# Esquema.net
KiCad netlist of a schematic drawn in EAGLE
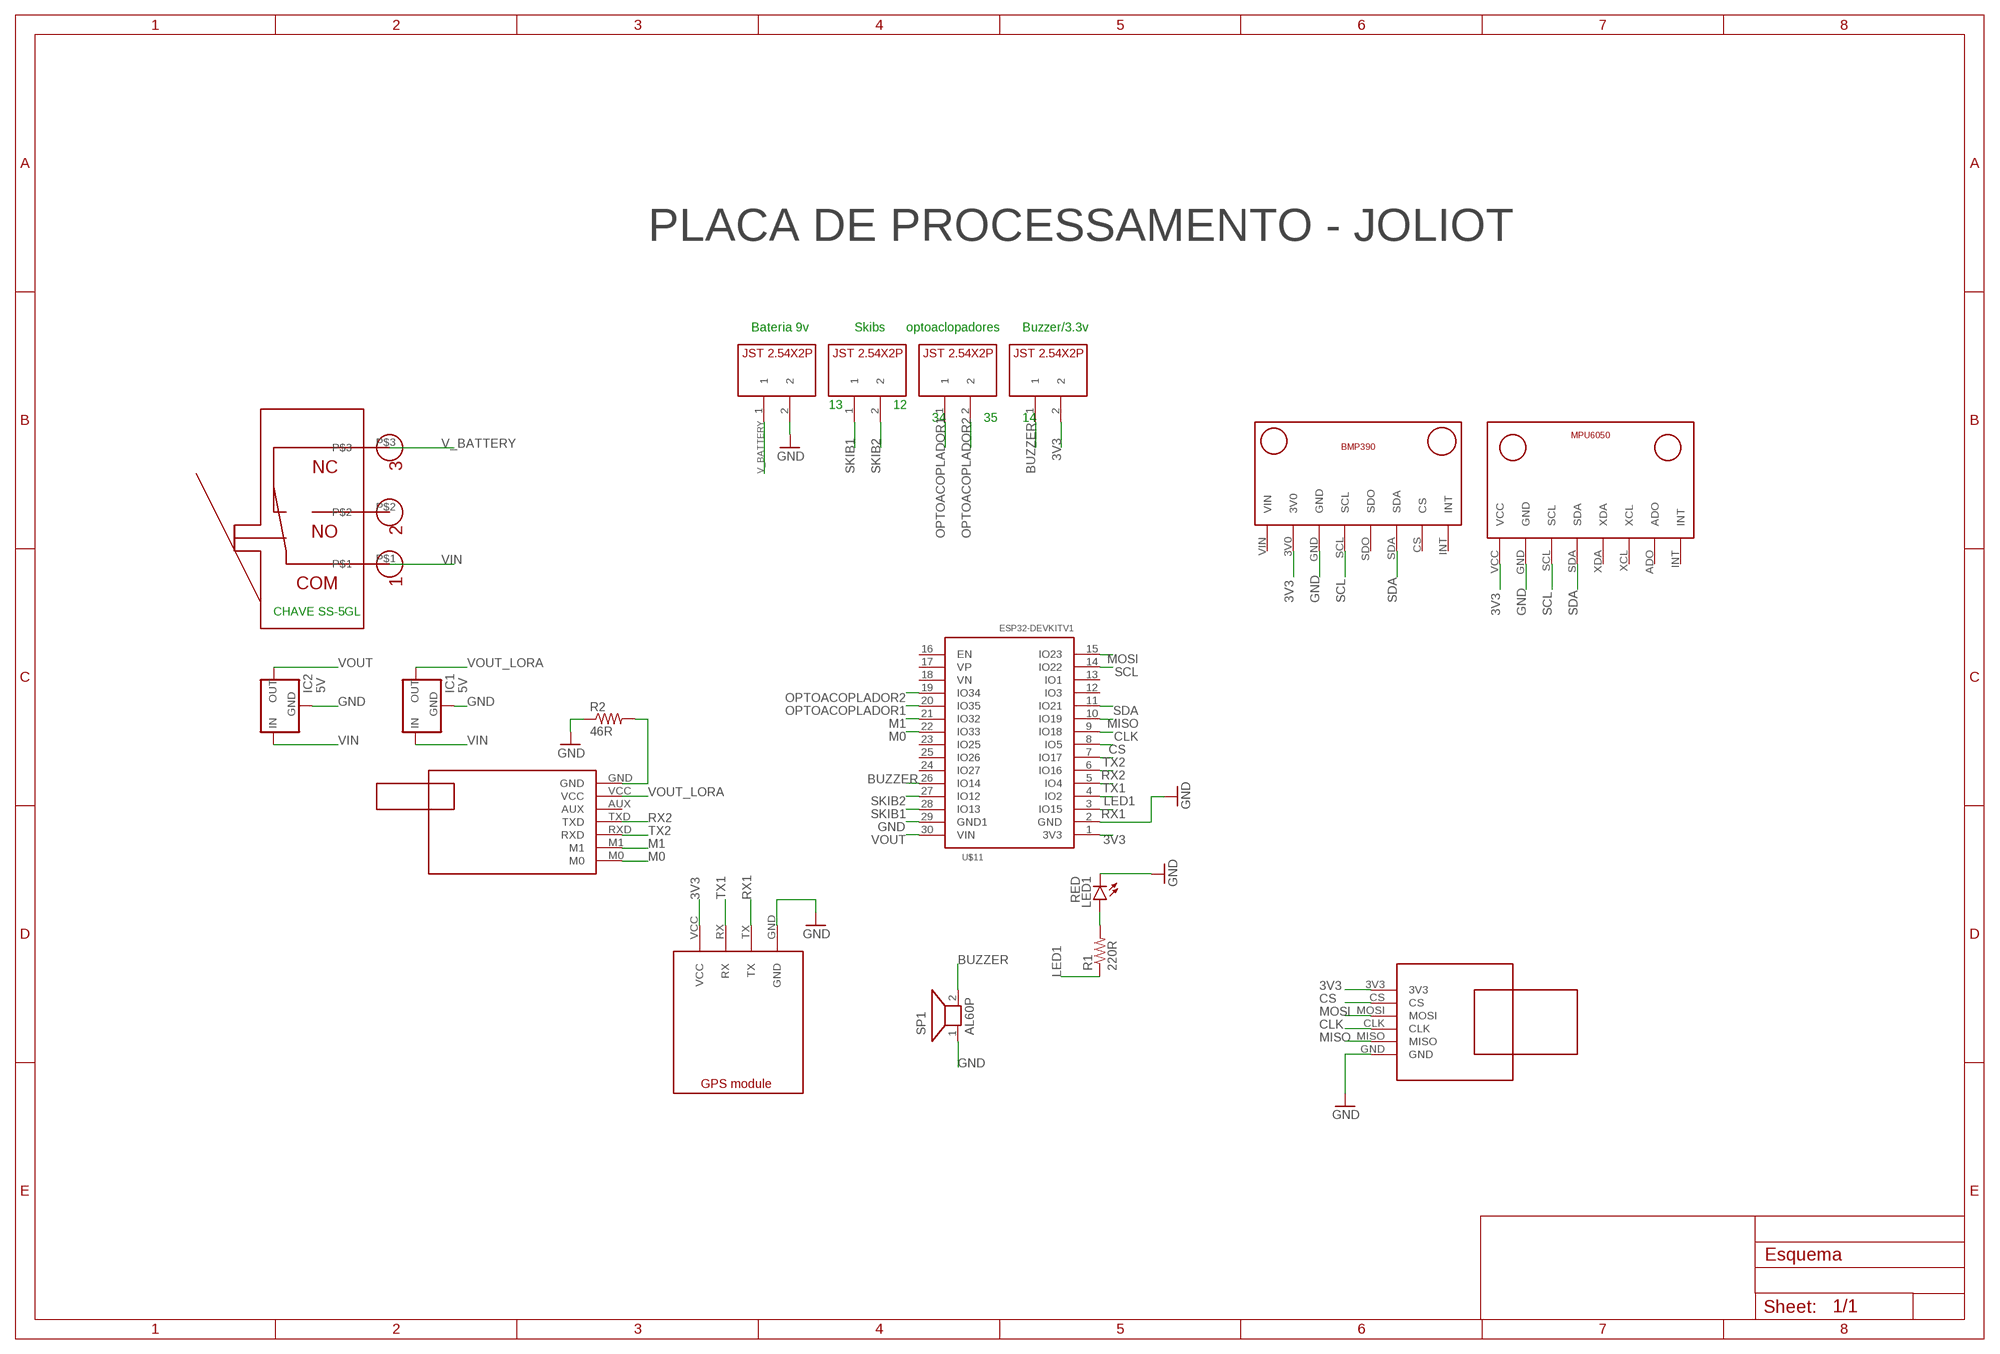
[diagram p0: schematic, sheet 1]

(export (version "E")
  (design (tool "Eeschema 10.0.6"))
  (components
    (comp (ref "IC1")
      (value "5V")
      (footprint "eagle-import:78XXL")
      (libsource (lib "eagle-import") (part "78XXL"))
    )
    (comp (ref "IC2")
      (value "5V")
      (footprint "eagle-import:78XXL")
      (libsource (lib "eagle-import") (part "78XXL"))
    )
    (comp (ref "LED1")
      (value "RED")
      (footprint "eagle-import:LED5MM")
      (libsource (lib "eagle-import") (part "LED5MM"))
    )
    (comp (ref "R1")
      (value "220R")
      (footprint "eagle-import:0309_12")
      (libsource (lib "eagle-import") (part "R-US_0309/12"))
    )
    (comp (ref "R2")
      (value "46R")
      (footprint "eagle-import:0309_12")
      (libsource (lib "eagle-import") (part "R-US_0309/12"))
    )
    (comp (ref "SP1")
      (value "AL60P")
      (footprint "eagle-import:AL60P")
      (libsource (lib "eagle-import") (part "AL60P"))
    )
    (comp (ref "U$1")
      (value "BMP390V1")
      (footprint "eagle-import:BMP390_FOOTPRINT")
      (libsource (lib "eagle-import") (part "BMP390V1"))
    )
    (comp (ref "U$2")
      (value "E22-400T30D")
      (footprint "eagle-import:E22-400T30D_FOOTPRINT")
      (libsource (lib "eagle-import") (part "E22-400T30D"))
    )
    (comp (ref "U$3")
      (value "GPS_MODULE")
      (footprint "eagle-import:GPS_MODULE_FOOTPRINT")
      (libsource (lib "eagle-import") (part "GPS_MODULE"))
    )
    (comp (ref "U$4")
      (value "JST2.54X2P")
      (footprint "eagle-import:JST2.54X2P_FOOTPRINT")
      (libsource (lib "eagle-import") (part "JST2.54X2P"))
    )
    (comp (ref "U$5")
      (value "JST2.54X2P")
      (footprint "eagle-import:JST2.54X2P_FOOTPRINT")
      (libsource (lib "eagle-import") (part "JST2.54X2P"))
    )
    (comp (ref "U$6")
      (value "JST2.54X2P")
      (footprint "eagle-import:JST2.54X2P_FOOTPRINT")
      (libsource (lib "eagle-import") (part "JST2.54X2P"))
    )
    (comp (ref "U$7")
      (value "JST2.54X2P")
      (footprint "eagle-import:JST2.54X2P_FOOTPRINT")
      (libsource (lib "eagle-import") (part "JST2.54X2P"))
    )
    (comp (ref "U$8")
      (value "MICROSD_SMALL_READER")
      (footprint "eagle-import:MICROSD_SMALL_READER_FOOTPRINT")
      (libsource (lib "eagle-import") (part "MICROSD_SMALL_READER"))
    )
    (comp (ref "U$9")
      (value "MPU6050V1")
      (footprint "eagle-import:MPU6050_FOOTPRINT")
      (libsource (lib "eagle-import") (part "MPU6050V1"))
    )
    (comp (ref "U$11")
      (value "ESP32DEVKITV1")
      (footprint "eagle-import:ESP32-DEVKITV1")
      (libsource (lib "eagle-import") (part "ESP32DEVKITV1"))
    )
    (comp (ref "U$12")
      (value "CHAVE_SS-5GL")
      (footprint "eagle-import:CHAVESS-5GL")
      (libsource (lib "eagle-import") (part "CHAVE_SS-5GL"))
    )
  )
  (nets
    (net (code "1") (name "/3V3") (class "Default")
      (node (ref "U$1") (pin "3V0") (pinfunction "3V0_3V0") (pintype "bidirectional"))
      (node (ref "U$11") (pin "1") (pinfunction "3V3_1") (pintype "bidirectional"))
      (node (ref "U$3") (pin "VCC") (pinfunction "VCC_VCC") (pintype "bidirectional"))
      (node (ref "U$4") (pin "2") (pinfunction "2_2") (pintype "bidirectional"))
      (node (ref "U$8") (pin "3V3") (pinfunction "3V3_3V3") (pintype "bidirectional"))
      (node (ref "U$9") (pin "VCC") (pinfunction "VCC_VCC") (pintype "bidirectional"))
    )
    (net (code "2") (name "/BUZZER") (class "Default")
      (node (ref "SP1") (pin "2") (pinfunction "2_2") (pintype "passive"))
      (node (ref "U$11") (pin "26") (pinfunction "IO14_26") (pintype "bidirectional"))
      (node (ref "U$4") (pin "1") (pinfunction "1_1") (pintype "bidirectional"))
    )
    (net (code "3") (name "/CLK") (class "Default")
      (node (ref "U$11") (pin "9") (pinfunction "IO18_9") (pintype "bidirectional"))
      (node (ref "U$8") (pin "CLK") (pinfunction "CLK_CLK") (pintype "bidirectional"))
    )
    (net (code "4") (name "/CS") (class "Default")
      (node (ref "U$11") (pin "8") (pinfunction "IO5_8") (pintype "bidirectional"))
      (node (ref "U$8") (pin "CS") (pinfunction "CS_CS") (pintype "bidirectional"))
    )
    (net (code "5") (name "/LED1") (class "Default")
      (node (ref "R1") (pin "1") (pinfunction "1_1") (pintype "passive"))
      (node (ref "U$11") (pin "4") (pinfunction "IO2_4") (pintype "bidirectional"))
    )
    (net (code "6") (name "/M0") (class "Default")
      (node (ref "U$11") (pin "22") (pinfunction "IO33_22") (pintype "bidirectional"))
      (node (ref "U$2") (pin "M0") (pinfunction "M0_M0") (pintype "bidirectional"))
    )
    (net (code "7") (name "/M1") (class "Default")
      (node (ref "U$11") (pin "21") (pinfunction "IO32_21") (pintype "bidirectional"))
      (node (ref "U$2") (pin "M1") (pinfunction "M1_M1") (pintype "bidirectional"))
    )
    (net (code "8") (name "/MISO") (class "Default")
      (node (ref "U$11") (pin "10") (pinfunction "IO19_10") (pintype "bidirectional"))
      (node (ref "U$8") (pin "MISO") (pinfunction "MISO_MISO") (pintype "bidirectional"))
    )
    (net (code "9") (name "/MOSI") (class "Default")
      (node (ref "U$11") (pin "15") (pinfunction "IO23_15") (pintype "bidirectional"))
      (node (ref "U$8") (pin "MOSI") (pinfunction "MOSI_MOSI") (pintype "bidirectional"))
    )
    (net (code "10") (name "/OPTOACOPLADOR1") (class "Default")
      (node (ref "U$11") (pin "20") (pinfunction "IO35_20") (pintype "bidirectional"))
      (node (ref "U$5") (pin "1") (pinfunction "1_1") (pintype "bidirectional"))
    )
    (net (code "11") (name "/OPTOACOPLADOR2") (class "Default")
      (node (ref "U$11") (pin "19") (pinfunction "IO34_19") (pintype "bidirectional"))
      (node (ref "U$5") (pin "2") (pinfunction "2_2") (pintype "bidirectional"))
    )
    (net (code "12") (name "/RX1") (class "Default")
      (node (ref "U$11") (pin "3") (pinfunction "IO15_3") (pintype "bidirectional"))
      (node (ref "U$3") (pin "TX") (pinfunction "TX_TX") (pintype "bidirectional"))
    )
    (net (code "13") (name "/RX2") (class "Default")
      (node (ref "U$11") (pin "6") (pinfunction "IO16_6") (pintype "bidirectional"))
      (node (ref "U$2") (pin "TXD") (pinfunction "TXD_TXD") (pintype "bidirectional"))
    )
    (net (code "14") (name "/SCL") (class "Default")
      (node (ref "U$1") (pin "SCL") (pinfunction "SCL_SCL") (pintype "bidirectional"))
      (node (ref "U$11") (pin "14") (pinfunction "IO22_14") (pintype "bidirectional"))
      (node (ref "U$9") (pin "SCL") (pinfunction "SCL_SCL") (pintype "bidirectional"))
    )
    (net (code "15") (name "/SDA") (class "Default")
      (node (ref "U$1") (pin "SDA") (pinfunction "SDA_SDA") (pintype "bidirectional"))
      (node (ref "U$11") (pin "11") (pinfunction "IO21_11") (pintype "bidirectional"))
      (node (ref "U$9") (pin "SDA") (pinfunction "SDA_SDA") (pintype "bidirectional"))
    )
    (net (code "16") (name "/SKIB1") (class "Default")
      (node (ref "U$11") (pin "28") (pinfunction "IO13_28") (pintype "bidirectional"))
      (node (ref "U$6") (pin "1") (pinfunction "1_1") (pintype "bidirectional"))
    )
    (net (code "17") (name "/SKIB2") (class "Default")
      (node (ref "U$11") (pin "27") (pinfunction "IO12_27") (pintype "bidirectional"))
      (node (ref "U$6") (pin "2") (pinfunction "2_2") (pintype "bidirectional"))
    )
    (net (code "18") (name "/TX1") (class "Default")
      (node (ref "U$11") (pin "5") (pinfunction "IO4_5") (pintype "bidirectional"))
      (node (ref "U$3") (pin "RX") (pinfunction "RX_RX") (pintype "bidirectional"))
    )
    (net (code "19") (name "/TX2") (class "Default")
      (node (ref "U$11") (pin "7") (pinfunction "IO17_7") (pintype "bidirectional"))
      (node (ref "U$2") (pin "RXD") (pinfunction "RXD_RXD") (pintype "bidirectional"))
    )
    (net (code "20") (name "/VIN") (class "Default")
      (node (ref "IC1") (pin "IN") (pinfunction "IN_IN") (pintype "input"))
      (node (ref "IC2") (pin "IN") (pinfunction "IN_IN") (pintype "input"))
      (node (ref "U$12") (pin "P$1") (pinfunction "P$1_P$1") (pintype "bidirectional"))
    )
    (net (code "21") (name "/VOUT") (class "Default")
      (node (ref "IC2") (pin "OUT") (pinfunction "OUT_OUT") (pintype "passive"))
      (node (ref "U$11") (pin "30") (pinfunction "VIN_30") (pintype "bidirectional"))
    )
    (net (code "22") (name "/VOUT_LORA") (class "Default")
      (node (ref "IC1") (pin "OUT") (pinfunction "OUT_OUT") (pintype "passive"))
      (node (ref "U$2") (pin "VCC") (pinfunction "VCC_VCC") (pintype "bidirectional"))
    )
    (net (code "23") (name "/V_BATTERY") (class "Default")
      (node (ref "U$12") (pin "P$3") (pinfunction "P$3_P$3") (pintype "bidirectional"))
      (node (ref "U$7") (pin "1") (pinfunction "1_1") (pintype "bidirectional"))
    )
    (net (code "24") (name "GND") (class "Default")
      (node (ref "IC1") (pin "GND") (pinfunction "GND_GND") (pintype "input"))
      (node (ref "IC2") (pin "GND") (pinfunction "GND_GND") (pintype "input"))
      (node (ref "LED1") (pin "K") (pinfunction "C_K") (pintype "passive"))
      (node (ref "R2") (pin "1") (pinfunction "1_1") (pintype "passive"))
      (node (ref "SP1") (pin "1") (pinfunction "1_1") (pintype "passive"))
      (node (ref "U$1") (pin "GND") (pinfunction "GND_GND") (pintype "bidirectional"))
      (node (ref "U$11") (pin "2") (pinfunction "GND_2") (pintype "bidirectional"))
      (node (ref "U$11") (pin "29") (pinfunction "GND1_29") (pintype "bidirectional"))
      (node (ref "U$3") (pin "GND") (pinfunction "GND_GND") (pintype "bidirectional"))
      (node (ref "U$7") (pin "2") (pinfunction "2_2") (pintype "bidirectional"))
      (node (ref "U$8") (pin "GND") (pinfunction "GND_GND") (pintype "bidirectional"))
      (node (ref "U$9") (pin "GND") (pinfunction "GND_GND") (pintype "bidirectional"))
    )
    (net (code "25") (name "Net-(LED1-PadA)") (class "Default")
      (node (ref "LED1") (pin "A") (pinfunction "A_A") (pintype "passive"))
      (node (ref "R1") (pin "2") (pinfunction "2_2") (pintype "passive"))
    )
    (net (code "26") (name "Net-(R2-Pad2)") (class "Default")
      (node (ref "R2") (pin "2") (pinfunction "2_2") (pintype "passive"))
      (node (ref "U$2") (pin "GND") (pinfunction "GND_GND") (pintype "bidirectional"))
    )
    (net (code "27") (name "unconnected-(U$1-PadCS)") (class "Default")
      (node (ref "U$1") (pin "CS") (pinfunction "CS_CS") (pintype "bidirectional"))
    )
    (net (code "28") (name "unconnected-(U$1-PadINT)") (class "Default")
      (node (ref "U$1") (pin "INT") (pinfunction "INT_INT") (pintype "bidirectional"))
    )
    (net (code "29") (name "unconnected-(U$1-PadSDO)") (class "Default")
      (node (ref "U$1") (pin "SDO") (pinfunction "SDO_SDO") (pintype "bidirectional"))
    )
    (net (code "30") (name "unconnected-(U$1-PadVIN)") (class "Default")
      (node (ref "U$1") (pin "VIN") (pinfunction "VIN_VIN") (pintype "bidirectional"))
    )
    (net (code "31") (name "unconnected-(U$2-PadAUX)") (class "Default")
      (node (ref "U$2") (pin "AUX") (pinfunction "AUX_AUX") (pintype "bidirectional"))
    )
    (net (code "32") (name "unconnected-(U$9-PadADO)") (class "Default")
      (node (ref "U$9") (pin "ADO") (pinfunction "ADO_ADO") (pintype "bidirectional"))
    )
    (net (code "33") (name "unconnected-(U$9-PadINT)") (class "Default")
      (node (ref "U$9") (pin "INT") (pinfunction "INT_INT") (pintype "bidirectional"))
    )
    (net (code "34") (name "unconnected-(U$9-PadXCL)") (class "Default")
      (node (ref "U$9") (pin "XCL") (pinfunction "XCL_XCL") (pintype "bidirectional"))
    )
    (net (code "35") (name "unconnected-(U$9-PadXDA)") (class "Default")
      (node (ref "U$9") (pin "XDA") (pinfunction "XDA_XDA") (pintype "bidirectional"))
    )
    (net (code "36") (name "unconnected-(U$11-EN-Pad16)") (class "Default")
      (node (ref "U$11") (pin "16") (pinfunction "EN_16") (pintype "bidirectional"))
    )
    (net (code "37") (name "unconnected-(U$11-IO1-Pad13)") (class "Default")
      (node (ref "U$11") (pin "13") (pinfunction "IO1_13") (pintype "bidirectional"))
    )
    (net (code "38") (name "unconnected-(U$11-IO3-Pad12)") (class "Default")
      (node (ref "U$11") (pin "12") (pinfunction "IO3_12") (pintype "bidirectional"))
    )
    (net (code "39") (name "unconnected-(U$11-IO25-Pad23)") (class "Default")
      (node (ref "U$11") (pin "23") (pinfunction "IO25_23") (pintype "bidirectional"))
    )
    (net (code "40") (name "unconnected-(U$11-IO26-Pad25)") (class "Default")
      (node (ref "U$11") (pin "25") (pinfunction "IO26_25") (pintype "bidirectional"))
    )
    (net (code "41") (name "unconnected-(U$11-IO27-Pad24)") (class "Default")
      (node (ref "U$11") (pin "24") (pinfunction "IO27_24") (pintype "bidirectional"))
    )
    (net (code "42") (name "unconnected-(U$11-VN-Pad18)") (class "Default")
      (node (ref "U$11") (pin "18") (pinfunction "VN_18") (pintype "bidirectional"))
    )
    (net (code "43") (name "unconnected-(U$11-VP-Pad17)") (class "Default")
      (node (ref "U$11") (pin "17") (pinfunction "VP_17") (pintype "bidirectional"))
    )
    (net (code "44") (name "unconnected-(U$12-PadP$2)") (class "Default")
      (node (ref "U$12") (pin "P$2") (pinfunction "P$2_P$2") (pintype "bidirectional"))
    )
  )
)
